# untitled.net
KiCad netlist of a schematic drawn in EAGLE
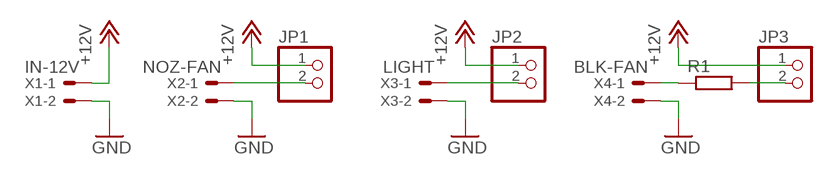
[diagram p0: schematic, sheet 1]

(export (version "E")
  (design (tool "Eeschema 10.0.6"))
  (components
    (comp (ref "JP1")
      (value "PINHD-1X2")
      (footprint "eagle-import:1X02")
      (libsource (lib "eagle-import") (part "PINHD-1X2"))
    )
    (comp (ref "JP2")
      (value "PINHD-1X2")
      (footprint "eagle-import:1X02")
      (libsource (lib "eagle-import") (part "PINHD-1X2"))
    )
    (comp (ref "JP3")
      (value "PINHD-1X2")
      (footprint "eagle-import:1X02")
      (libsource (lib "eagle-import") (part "PINHD-1X2"))
    )
    (comp (ref "R1")
      (value "R-EU_0204/7")
      (footprint "eagle-import:0204_7")
      (libsource (lib "eagle-import") (part "R-EU_0204/7"))
    )
    (comp (ref "X1")
      (value "IN-12V")
      (footprint "eagle-import:JST-XH-02-PACKAGE-LONG-PAD")
      (libsource (lib "eagle-import") (part "JST-XH-02-PIN-LONG-PAD"))
    )
    (comp (ref "X2")
      (value "NOZ-FAN")
      (footprint "eagle-import:JST-XH-02-PACKAGE-LONG-PAD")
      (libsource (lib "eagle-import") (part "JST-XH-02-PIN-LONG-PAD"))
    )
    (comp (ref "X3")
      (value "LIGHT")
      (footprint "eagle-import:JST-XH-02-PACKAGE-LONG-PAD")
      (libsource (lib "eagle-import") (part "JST-XH-02-PIN-LONG-PAD"))
    )
    (comp (ref "X4")
      (value "BLK-FAN")
      (footprint "eagle-import:JST-XH-02-PACKAGE-LONG-PAD")
      (libsource (lib "eagle-import") (part "JST-XH-02-PIN-LONG-PAD"))
    )
  )
  (nets
    (net (code "1") (name "+12V") (class "Default")
      (node (ref "JP1") (pin "1") (pinfunction "1_1") (pintype "passive"))
      (node (ref "JP2") (pin "1") (pinfunction "1_1") (pintype "passive"))
      (node (ref "JP3") (pin "1") (pinfunction "1_1") (pintype "passive"))
      (node (ref "X1") (pin "1") (pinfunction "S_1") (pintype "passive"))
    )
    (net (code "2") (name "GND") (class "Default")
      (node (ref "X1") (pin "2") (pinfunction "S_2") (pintype "passive"))
      (node (ref "X2") (pin "2") (pinfunction "S_2") (pintype "passive"))
      (node (ref "X3") (pin "2") (pinfunction "S_2") (pintype "passive"))
      (node (ref "X4") (pin "2") (pinfunction "S_2") (pintype "passive"))
    )
    (net (code "3") (name "Net-(JP3-Pad2)") (class "Default")
      (node (ref "JP3") (pin "2") (pinfunction "2_2") (pintype "passive"))
      (node (ref "R1") (pin "2") (pinfunction "2_2") (pintype "passive"))
    )
    (net (code "4") (name "Net-(X2A-S)") (class "Default")
      (node (ref "JP1") (pin "2") (pinfunction "2_2") (pintype "passive"))
      (node (ref "X2") (pin "1") (pinfunction "S_1") (pintype "passive"))
    )
    (net (code "5") (name "Net-(X3A-S)") (class "Default")
      (node (ref "JP2") (pin "2") (pinfunction "2_2") (pintype "passive"))
      (node (ref "X3") (pin "1") (pinfunction "S_1") (pintype "passive"))
    )
    (net (code "6") (name "Net-(X4A-S)") (class "Default")
      (node (ref "R1") (pin "1") (pinfunction "1_1") (pintype "passive"))
      (node (ref "X4") (pin "1") (pinfunction "S_1") (pintype "passive"))
    )
  )
)
